# db9-horizontal-autoband-R1.net
KiCad netlist of a schematic drawn in EAGLE
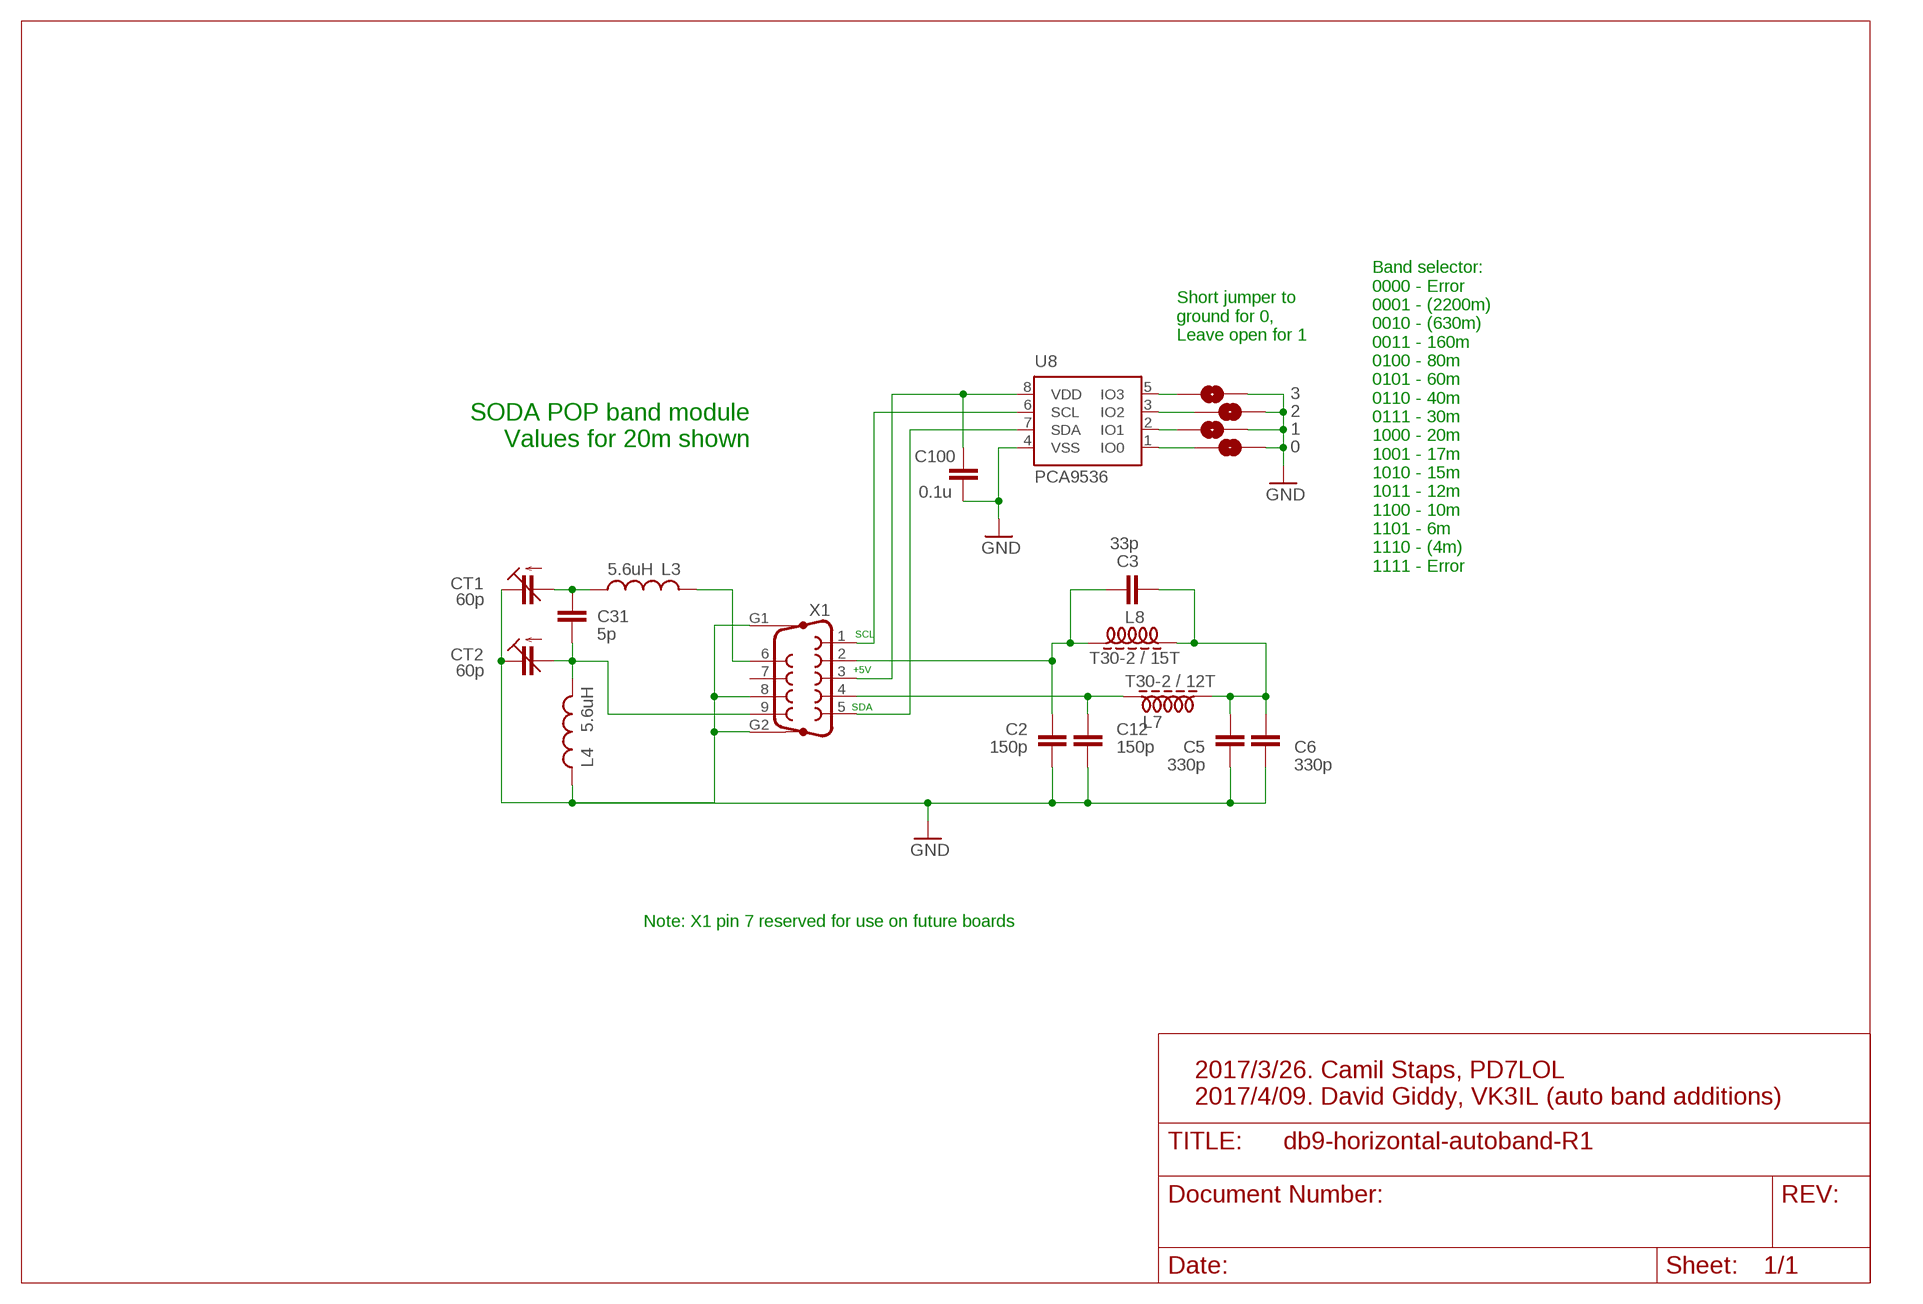
[diagram p0: schematic, sheet 1]

(export (version "E")
  (design (tool "Eeschema 10.0.6"))
  (components
    (comp (ref "0") (value "SJ") (footprint "eagle-import:SJ") (libsource (lib "eagle-import") (part "SJ")))
    (comp (ref "1") (value "SJ") (footprint "eagle-import:SJ") (libsource (lib "eagle-import") (part "SJ")))
    (comp (ref "2") (value "SJ") (footprint "eagle-import:SJ") (libsource (lib "eagle-import") (part "SJ")))
    (comp (ref "3") (value "SJ") (footprint "eagle-import:SJ") (libsource (lib "eagle-import") (part "SJ")))
    (comp (ref "C2")
      (value "150p")
      (footprint "eagle-import:C1206K")
      (libsource (lib "eagle-import") (part "C-EUC1206K"))
    )
    (comp (ref "C3")
      (value "33p")
      (footprint "eagle-import:C1206K")
      (libsource (lib "eagle-import") (part "C-EUC1206K"))
    )
    (comp (ref "C5")
      (value "330p")
      (footprint "eagle-import:C1206K")
      (libsource (lib "eagle-import") (part "C-EUC1206K"))
    )
    (comp (ref "C6")
      (value "330p")
      (footprint "eagle-import:C1206K")
      (libsource (lib "eagle-import") (part "C-EUC1206K"))
    )
    (comp (ref "C12")
      (value "150p")
      (footprint "eagle-import:C1206K")
      (libsource (lib "eagle-import") (part "C-EUC1206K"))
    )
    (comp (ref "C31")
      (value "5p")
      (footprint "eagle-import:C0805K")
      (libsource (lib "eagle-import") (part "C-EUC0805K"))
    )
    (comp (ref "C100")
      (value "0.1u")
      (footprint "eagle-import:C0805K")
      (libsource (lib "eagle-import") (part "C-EUC0805K"))
    )
    (comp (ref "CT1")
      (value "60p")
      (footprint "eagle-import:CTRIMTZ03")
      (libsource (lib "eagle-import") (part "C-TRIMMTZ03"))
    )
    (comp (ref "CT2")
      (value "60p")
      (footprint "eagle-import:CTRIMTZ03")
      (libsource (lib "eagle-import") (part "C-TRIMMTZ03"))
    )
    (comp (ref "L3")
      (value "5.6uH")
      (footprint "eagle-import:L2012C")
      (libsource (lib "eagle-import") (part "L-USL2012C"))
    )
    (comp (ref "L4")
      (value "5.6uH")
      (footprint "eagle-import:L2012C")
      (libsource (lib "eagle-import") (part "L-USL2012C"))
    )
    (comp (ref "L7")
      (value "T30-2 / 12T")
      (footprint "eagle-import:T30-2-28AWG-15T")
      (libsource (lib "eagle-import") (part "INDUCTORT30-2-28AWG-15T"))
    )
    (comp (ref "L8")
      (value "T30-2 / 15T")
      (footprint "eagle-import:T30-2-28AWG-15T")
      (libsource (lib "eagle-import") (part "INDUCTORT30-2-28AWG-15T"))
    )
    (comp (ref "U8")
      (value "PCA9536")
      (footprint "eagle-import:SO8")
      (libsource (lib "eagle-import") (part "PCA9536"))
    )
    (comp (ref "X1")
      (value "F09VP")
      (footprint "eagle-import:F09VP")
      (libsource (lib "eagle-import") (part "F09VP"))
    )
  )
  (nets
    (net (code "1") (name "GND") (class "Default")
      (node (ref "0") (pin "2") (pinfunction "2_2") (pintype "passive"))
      (node (ref "1") (pin "2") (pinfunction "2_2") (pintype "passive"))
      (node (ref "2") (pin "2") (pinfunction "2_2") (pintype "passive"))
      (node (ref "3") (pin "2") (pinfunction "2_2") (pintype "passive"))
      (node (ref "C100") (pin "2") (pinfunction "2_2") (pintype "passive"))
      (node (ref "C12") (pin "2") (pinfunction "2_2") (pintype "passive"))
      (node (ref "C2") (pin "2") (pinfunction "2_2") (pintype "passive"))
      (node (ref "C5") (pin "2") (pinfunction "2_2") (pintype "passive"))
      (node (ref "C6") (pin "2") (pinfunction "2_2") (pintype "passive"))
      (node (ref "CT1") (pin "1") (pinfunction "E_1") (pintype "passive"))
      (node (ref "CT2") (pin "1") (pinfunction "E_1") (pintype "passive"))
      (node (ref "L4") (pin "2") (pinfunction "2_2") (pintype "passive"))
      (node (ref "U8") (pin "4") (pinfunction "VSS_4") (pintype "power_in"))
      (node (ref "X1") (pin "8") (pinfunction "8_8") (pintype "passive"))
      (node (ref "X1") (pin "G1") (pinfunction "G1_G1") (pintype "passive"))
      (node (ref "X1") (pin "G2") (pinfunction "G2_G2") (pintype "passive"))
    )
    (net (code "2") (name "Net-(CT1-A)") (class "Default")
      (node (ref "C31") (pin "1") (pinfunction "1_1") (pintype "passive"))
      (node (ref "CT1") (pin "2") (pinfunction "A_2") (pintype "passive"))
      (node (ref "L3") (pin "2") (pinfunction "2_2") (pintype "passive"))
    )
    (net (code "3") (name "Net-(CT2-A)") (class "Default")
      (node (ref "C31") (pin "2") (pinfunction "2_2") (pintype "passive"))
      (node (ref "CT2") (pin "2") (pinfunction "A_2") (pintype "passive"))
      (node (ref "L4") (pin "1") (pinfunction "1_1") (pintype "passive"))
      (node (ref "X1") (pin "9") (pinfunction "9_9") (pintype "passive"))
    )
    (net (code "4") (name "Net-(L3-Pad1)") (class "Default")
      (node (ref "L3") (pin "1") (pinfunction "1_1") (pintype "passive"))
      (node (ref "X1") (pin "6") (pinfunction "6_6") (pintype "passive"))
    )
    (net (code "5") (name "Net-(L7-1)") (class "Default")
      (node (ref "C12") (pin "1") (pinfunction "1_1") (pintype "passive"))
      (node (ref "L7") (pin "P$1") (pinfunction "1_P$1") (pintype "passive"))
      (node (ref "X1") (pin "4") (pinfunction "4_4") (pintype "passive"))
    )
    (net (code "6") (name "Net-(L7-2)") (class "Default")
      (node (ref "C3") (pin "2") (pinfunction "2_2") (pintype "passive"))
      (node (ref "C5") (pin "1") (pinfunction "1_1") (pintype "passive"))
      (node (ref "C6") (pin "1") (pinfunction "1_1") (pintype "passive"))
      (node (ref "L7") (pin "P$2") (pinfunction "2_P$2") (pintype "passive"))
      (node (ref "L8") (pin "P$2") (pinfunction "2_P$2") (pintype "passive"))
    )
    (net (code "7") (name "Net-(L8-1)") (class "Default")
      (node (ref "C2") (pin "1") (pinfunction "1_1") (pintype "passive"))
      (node (ref "C3") (pin "1") (pinfunction "1_1") (pintype "passive"))
      (node (ref "L8") (pin "P$1") (pinfunction "1_P$1") (pintype "passive"))
      (node (ref "X1") (pin "2") (pinfunction "2_2") (pintype "passive"))
    )
    (net (code "8") (name "Net-(U8-IO0)") (class "Default")
      (node (ref "0") (pin "1") (pinfunction "1_1") (pintype "passive"))
      (node (ref "U8") (pin "1") (pinfunction "IO0_1") (pintype "bidirectional"))
    )
    (net (code "9") (name "Net-(U8-IO1)") (class "Default")
      (node (ref "1") (pin "1") (pinfunction "1_1") (pintype "passive"))
      (node (ref "U8") (pin "2") (pinfunction "IO1_2") (pintype "bidirectional"))
    )
    (net (code "10") (name "Net-(U8-IO2)") (class "Default")
      (node (ref "2") (pin "1") (pinfunction "1_1") (pintype "passive"))
      (node (ref "U8") (pin "3") (pinfunction "IO2_3") (pintype "bidirectional"))
    )
    (net (code "11") (name "Net-(U8-IO3)") (class "Default")
      (node (ref "3") (pin "1") (pinfunction "1_1") (pintype "passive"))
      (node (ref "U8") (pin "5") (pinfunction "IO3_5") (pintype "bidirectional"))
    )
    (net (code "12") (name "Net-(U8-SCL)") (class "Default")
      (node (ref "U8") (pin "6") (pinfunction "SCL_6") (pintype "input"))
      (node (ref "X1") (pin "1") (pinfunction "1_1") (pintype "passive"))
    )
    (net (code "13") (name "Net-(U8-SDA)") (class "Default")
      (node (ref "U8") (pin "7") (pinfunction "SDA_7") (pintype "bidirectional"))
      (node (ref "X1") (pin "5") (pinfunction "5_5") (pintype "passive"))
    )
    (net (code "14") (name "Net-(U8-VDD)") (class "Default")
      (node (ref "C100") (pin "1") (pinfunction "1_1") (pintype "passive"))
      (node (ref "U8") (pin "8") (pinfunction "VDD_8") (pintype "power_in"))
      (node (ref "X1") (pin "3") (pinfunction "3_3") (pintype "passive"))
    )
    (net (code "15") (name "unconnected-(X1-Pad7)") (class "Default")
      (node (ref "X1") (pin "7") (pinfunction "7_7") (pintype "passive"))
    )
  )
)
